# Downloader_1_3.net
KiCad netlist of a schematic drawn in EAGLE
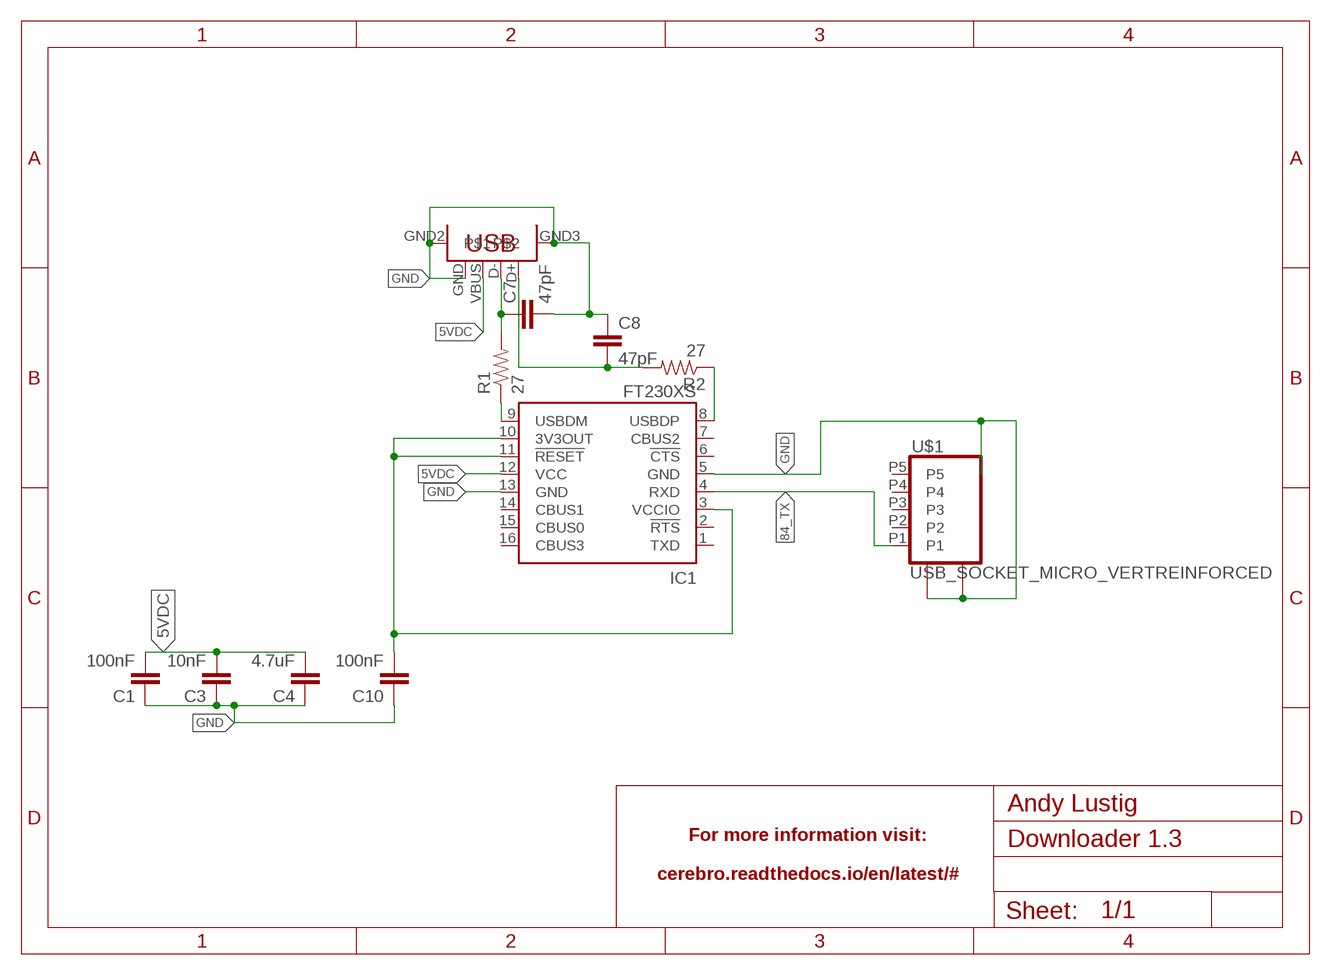
[diagram p0: schematic, sheet 1]

(export (version "E")
  (design (tool "Eeschema 10.0.6"))
  (components
    (comp (ref "C1")
      (value "100nF")
      (footprint "eagle-import:0805")
      (libsource (lib "eagle-import") (part "CAP0805"))
    )
    (comp (ref "C3")
      (value "10nF")
      (footprint "eagle-import:0805")
      (libsource (lib "eagle-import") (part "CAP0805"))
    )
    (comp (ref "C4")
      (value "4.7uF")
      (footprint "eagle-import:0805")
      (libsource (lib "eagle-import") (part "CAP0805"))
    )
    (comp (ref "C7")
      (value "47pF")
      (footprint "eagle-import:0805")
      (libsource (lib "eagle-import") (part "CAP0805"))
    )
    (comp (ref "C8")
      (value "47pF")
      (footprint "eagle-import:0805")
      (libsource (lib "eagle-import") (part "CAP0805"))
    )
    (comp (ref "C10")
      (value "100nF")
      (footprint "eagle-import:0805")
      (libsource (lib "eagle-import") (part "CAP0805"))
    )
    (comp (ref "IC1")
      (value "FT230XS")
      (footprint "eagle-import:SSOP16")
      (libsource (lib "eagle-import") (part "FT230XS"))
    )
    (comp (ref "JP1")
      (value "USB-A-H")
      (footprint "eagle-import:USB-A-H")
      (libsource (lib "eagle-import") (part "USB-A-H"))
    )
    (comp (ref "R1")
      (value "27")
      (footprint "eagle-import:0805")
      (libsource (lib "eagle-import") (part "RESISTOR0805-RES"))
    )
    (comp (ref "R2")
      (value "27")
      (footprint "eagle-import:0805")
      (libsource (lib "eagle-import") (part "RESISTOR0805-RES"))
    )
    (comp (ref "U$1")
      (value "USB_SOCKET_MICRO_VERTREINFORCED")
      (footprint "eagle-import:USB_HORZ_REINFORCED_MICRO")
      (libsource (lib "eagle-import") (part "USB_SOCKET_MICRO_VERTREINFORCED"))
    )
  )
  (nets
    (net (code "1") (name "5VDC") (class "Default")
      (node (ref "C1") (pin "2") (pinfunction "2_2") (pintype "passive"))
      (node (ref "C3") (pin "2") (pinfunction "2_2") (pintype "passive"))
      (node (ref "C4") (pin "2") (pinfunction "2_2") (pintype "passive"))
      (node (ref "IC1") (pin "12") (pinfunction "VCC_12") (pintype "power_in"))
      (node (ref "JP1") (pin "VBUS") (pinfunction "VBUS_VBUS") (pintype "bidirectional"))
    )
    (net (code "2") (name "84_TX") (class "Default")
      (node (ref "IC1") (pin "4") (pinfunction "RXD_4") (pintype "input"))
      (node (ref "U$1") (pin "P1") (pinfunction "P1_P1") (pintype "bidirectional"))
    )
    (net (code "3") (name "GND") (class "Default")
      (node (ref "C1") (pin "1") (pinfunction "1_1") (pintype "passive"))
      (node (ref "C10") (pin "1") (pinfunction "1_1") (pintype "passive"))
      (node (ref "C3") (pin "1") (pinfunction "1_1") (pintype "passive"))
      (node (ref "C4") (pin "1") (pinfunction "1_1") (pintype "passive"))
      (node (ref "C7") (pin "2") (pinfunction "2_2") (pintype "passive"))
      (node (ref "C8") (pin "1") (pinfunction "1_1") (pintype "passive"))
      (node (ref "IC1") (pin "13") (pinfunction "GND_13") (pintype "power_in"))
      (node (ref "IC1") (pin "5") (pinfunction "GND_5") (pintype "power_in"))
      (node (ref "JP1") (pin "GND") (pinfunction "GND_GND") (pintype "bidirectional"))
      (node (ref "JP1") (pin "GND2") (pinfunction "P$1_GND2") (pintype "bidirectional"))
      (node (ref "JP1") (pin "GND3") (pinfunction "P$2_GND3") (pintype "bidirectional"))
      (node (ref "U$1") (pin "G1") (pinfunction "P$1_G1") (pintype "bidirectional"))
      (node (ref "U$1") (pin "G2") (pinfunction "P$1_G2") (pintype "bidirectional"))
      (node (ref "U$1") (pin "P$1") (pinfunction "P$2_P$1") (pintype "bidirectional"))
      (node (ref "U$1") (pin "P$2") (pinfunction "P$2_P$2") (pintype "bidirectional"))
    )
    (net (code "4") (name "Net-(C7-Pad1)") (class "Default")
      (node (ref "C7") (pin "1") (pinfunction "1_1") (pintype "passive"))
      (node (ref "JP1") (pin "D-") (pinfunction "D-_D-") (pintype "bidirectional"))
      (node (ref "R1") (pin "2") (pinfunction "2_2") (pintype "passive"))
    )
    (net (code "5") (name "Net-(C8-Pad2)") (class "Default")
      (node (ref "C8") (pin "2") (pinfunction "2_2") (pintype "passive"))
      (node (ref "JP1") (pin "D+") (pinfunction "D+_D+") (pintype "bidirectional"))
      (node (ref "R2") (pin "2") (pinfunction "2_2") (pintype "passive"))
    )
    (net (code "6") (name "Net-(IC1-3V3OUT)") (class "Default")
      (node (ref "C10") (pin "2") (pinfunction "2_2") (pintype "passive"))
      (node (ref "IC1") (pin "10") (pinfunction "3V3OUT_10") (pintype "output"))
      (node (ref "IC1") (pin "11") (pinfunction "~{RESET}_11") (pintype "input"))
      (node (ref "IC1") (pin "3") (pinfunction "VCCIO_3") (pintype "power_in"))
    )
    (net (code "7") (name "Net-(IC1-USBDM)") (class "Default")
      (node (ref "IC1") (pin "9") (pinfunction "USBDM_9") (pintype "input"))
      (node (ref "R1") (pin "1") (pinfunction "1_1") (pintype "passive"))
    )
    (net (code "8") (name "Net-(IC1-USBDP)") (class "Default")
      (node (ref "IC1") (pin "8") (pinfunction "USBDP_8") (pintype "input"))
      (node (ref "R2") (pin "1") (pinfunction "1_1") (pintype "passive"))
    )
    (net (code "9") (name "unconnected-(IC1-CBUS0-Pad15)") (class "Default")
      (node (ref "IC1") (pin "15") (pinfunction "CBUS0_15") (pintype "bidirectional"))
    )
    (net (code "10") (name "unconnected-(IC1-CBUS1-Pad14)") (class "Default")
      (node (ref "IC1") (pin "14") (pinfunction "CBUS1_14") (pintype "bidirectional"))
    )
    (net (code "11") (name "unconnected-(IC1-CBUS2-Pad7)") (class "Default")
      (node (ref "IC1") (pin "7") (pinfunction "CBUS2_7") (pintype "bidirectional"))
    )
    (net (code "12") (name "unconnected-(IC1-CBUS3-Pad16)") (class "Default")
      (node (ref "IC1") (pin "16") (pinfunction "CBUS3_16") (pintype "bidirectional"))
    )
    (net (code "13") (name "unconnected-(IC1-TXD-Pad1)") (class "Default")
      (node (ref "IC1") (pin "1") (pinfunction "TXD_1") (pintype "output"))
    )
    (net (code "14") (name "unconnected-(IC1-~{CTS}-Pad6)") (class "Default")
      (node (ref "IC1") (pin "6") (pinfunction "~{CTS}_6") (pintype "input"))
    )
    (net (code "15") (name "unconnected-(IC1-~{RTS}-Pad2)") (class "Default")
      (node (ref "IC1") (pin "2") (pinfunction "~{RTS}_2") (pintype "output"))
    )
    (net (code "16") (name "unconnected-(U$1-PadP2)") (class "Default")
      (node (ref "U$1") (pin "P2") (pinfunction "P2_P2") (pintype "bidirectional"))
    )
    (net (code "17") (name "unconnected-(U$1-PadP3)") (class "Default")
      (node (ref "U$1") (pin "P3") (pinfunction "P3_P3") (pintype "bidirectional"))
    )
    (net (code "18") (name "unconnected-(U$1-PadP4)") (class "Default")
      (node (ref "U$1") (pin "P4") (pinfunction "P4_P4") (pintype "bidirectional"))
    )
    (net (code "19") (name "unconnected-(U$1-PadP5)") (class "Default")
      (node (ref "U$1") (pin "P5") (pinfunction "P5_P5") (pintype "bidirectional"))
    )
  )
)
